# 3V3_LDO.net
KiCad netlist of a schematic drawn in Altium Designer
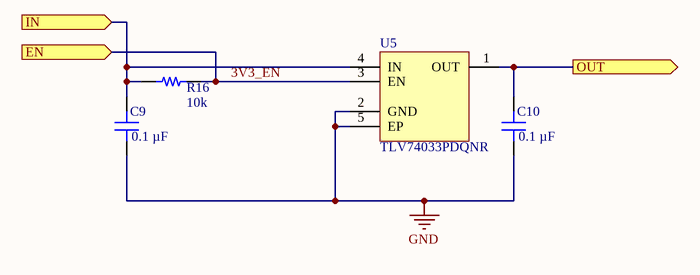
[diagram p0: 3V3_LDO.SchDoc]

(export (version "E")
  (design (tool "Eeschema 10.0.6"))
  (components
    (comp (ref "C9")
      (value "0.1 µF")
      (footprint "CAP 0402_1005")
      (description "CAP CER 0.1UF 16V X7R 0402")
      (fields (field (name "PART NUMBER") "C0402C104K4RACAUTO") (field (name "MANUFACTURER") "KEMET"))
      (libsource (lib "Celestial Altium Library - altium_library") (part "Capacitor"))
    )
    (comp (ref "C10")
      (value "0.1 µF")
      (footprint "CAP 0402_1005")
      (description "CAP CER 0.1UF 16V X7R 0402")
      (fields (field (name "PART NUMBER") "C0402C104K4RACAUTO") (field (name "MANUFACTURER") "KEMET"))
      (libsource (lib "Celestial Altium Library - altium_library") (part "Capacitor"))
    )
    (comp (ref "R16")
      (value "10k")
      (footprint "RES 0402_1005")
      (description "RES 5.62K OHM 0.1% 1/10W 0402")
      (fields
        (field (name "PART NUMBER") "RP73PF1E5K62BTD")
        (field (name "MANUFACTURER") "TE Connectivity Passive Product")
      )
      (libsource (lib "Celestial Altium Library - altium_library") (part "Resistor"))
    )
    (comp (ref "U5")
      (value "TLV74033PDQNR")
      (footprint "XDFN-4")
      (description "3.3V LDO")
      (libsource (lib "IC") (part "TLV74033PDQNR"))
    )
  )
  (nets
    (net (code "1") (name "/3V3_EN") (class "Default")
      (node (ref "R16") (pin "2") (pinfunction "2_2") (pintype "passive"))
      (node (ref "U5") (pin "3") (pinfunction "EN_3") (pintype "passive"))
    )
    (net (code "2") (name "/IN") (class "Default")
      (node (ref "C9") (pin "2") (pinfunction "2_2") (pintype "passive"))
      (node (ref "R16") (pin "1") (pinfunction "1_1") (pintype "passive"))
      (node (ref "U5") (pin "4") (pinfunction "IN_4") (pintype "passive"))
    )
    (net (code "3") (name "/OUT") (class "Default")
      (node (ref "C10") (pin "2") (pinfunction "2_2") (pintype "passive"))
      (node (ref "U5") (pin "1") (pinfunction "OUT_1") (pintype "passive"))
    )
    (net (code "4") (name "GND") (class "Default")
      (node (ref "C10") (pin "1") (pinfunction "1_1") (pintype "passive"))
      (node (ref "C9") (pin "1") (pinfunction "1_1") (pintype "passive"))
      (node (ref "U5") (pin "2") (pinfunction "GND_2") (pintype "passive"))
      (node (ref "U5") (pin "5") (pinfunction "EP_5") (pintype "passive"))
    )
  )
)
